# relay_dip_v01.net
KiCad netlist of a schematic drawn in EAGLE
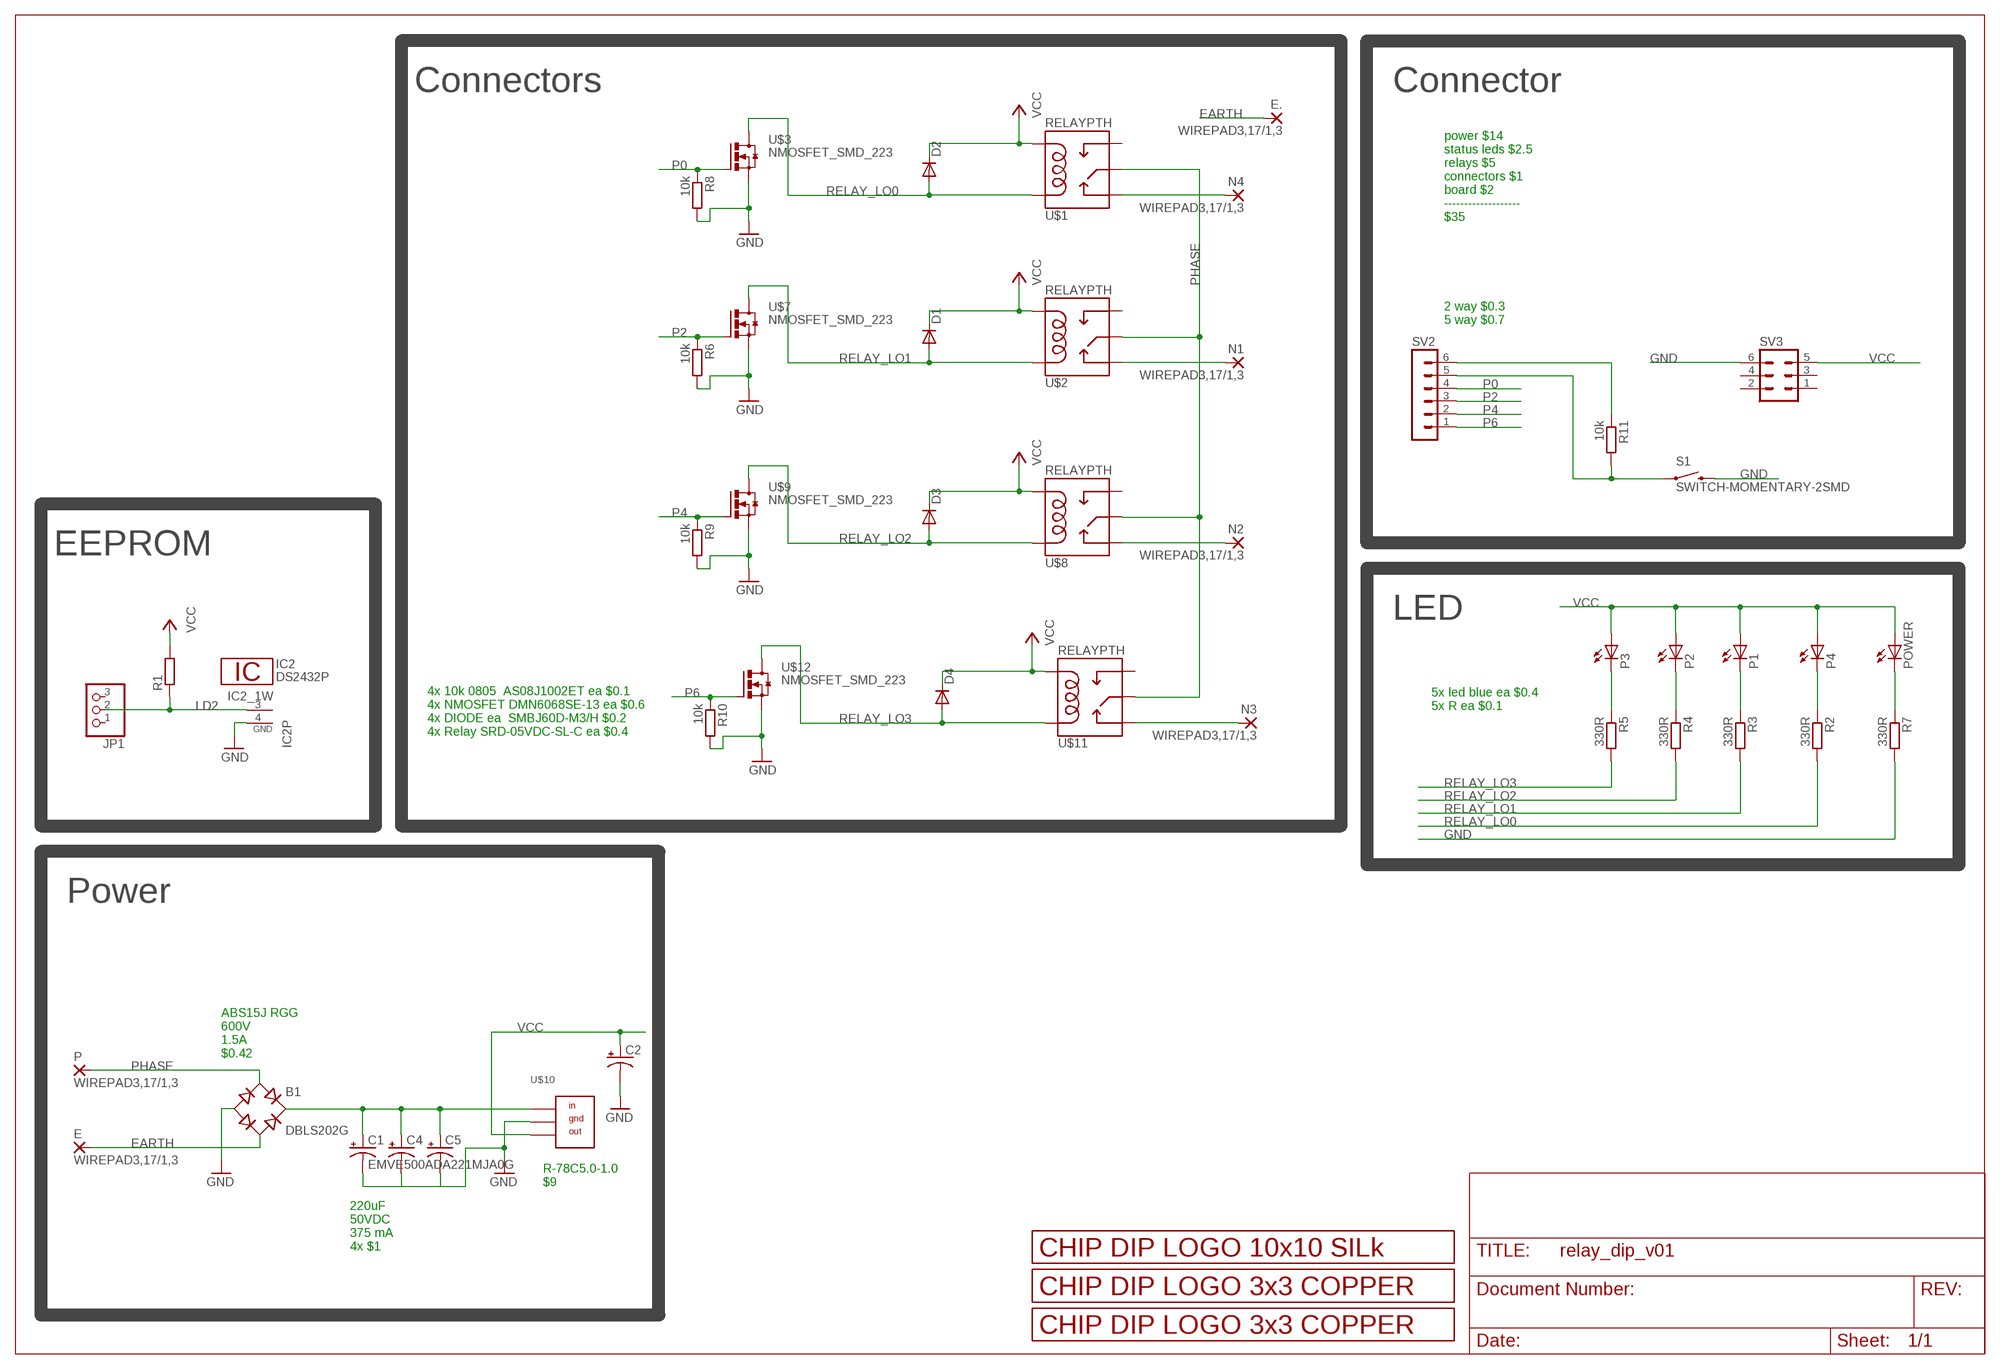
[diagram p0: schematic, sheet 1]

(export (version "E")
  (design (tool "Eeschema 10.0.6"))
  (components
    (comp (ref "B1")
      (value "DBLS202G")
      (footprint "eagle-import:DBS")
      (libsource (lib "eagle-import") (part "DB?GLS202"))
    )
    (comp (ref "C1")
      (value "EMVE500ADA221MJA0G")
      (footprint "eagle-import:150CLZ-0810")
      (libsource (lib "eagle-import") (part "CPOL-US150CLZ-0810"))
    )
    (comp (ref "C2")
      (value "CPOL-US150CLZ-0810")
      (footprint "eagle-import:150CLZ-0810")
      (libsource (lib "eagle-import") (part "CPOL-US150CLZ-0810"))
    )
    (comp (ref "C4")
      (value "CPOL-US150CLZ-0810")
      (footprint "eagle-import:150CLZ-0810")
      (libsource (lib "eagle-import") (part "CPOL-US150CLZ-0810"))
    )
    (comp (ref "C5")
      (value "CPOL-US150CLZ-0810")
      (footprint "eagle-import:150CLZ-0810")
      (libsource (lib "eagle-import") (part "CPOL-US150CLZ-0810"))
    )
    (comp (ref "D1")
      (value "DIODE-SMB")
      (footprint "eagle-import:SMB")
      (libsource (lib "eagle-import") (part "DIODE-SMB"))
    )
    (comp (ref "D2")
      (value "DIODE-SMB")
      (footprint "eagle-import:SMB")
      (libsource (lib "eagle-import") (part "DIODE-SMB"))
    )
    (comp (ref "D3")
      (value "DIODE-SMB")
      (footprint "eagle-import:SMB")
      (libsource (lib "eagle-import") (part "DIODE-SMB"))
    )
    (comp (ref "D4")
      (value "DIODE-SMB")
      (footprint "eagle-import:SMB")
      (libsource (lib "eagle-import") (part "DIODE-SMB"))
    )
    (comp (ref "E")
      (value "WIREPAD3,17/1,3")
      (footprint "eagle-import:3,17_1,3")
      (libsource (lib "eagle-import") (part "WIREPAD3,17/1,3"))
    )
    (comp (ref "E.")
      (value "WIREPAD3,17/1,3")
      (footprint "eagle-import:3,17_1,3")
      (libsource (lib "eagle-import") (part "WIREPAD3,17/1,3"))
    )
    (comp (ref "IC2")
      (value "DS2432P")
      (footprint "eagle-import:TSOC6")
      (libsource (lib "eagle-import") (part "DS2432P"))
    )
    (comp (ref "JP1")
      (value "PINHD-1X3")
      (footprint "eagle-import:1X03")
      (libsource (lib "eagle-import") (part "PINHD-1X3"))
    )
    (comp (ref "N1")
      (value "WIREPAD3,17/1,3")
      (footprint "eagle-import:3,17_1,3")
      (libsource (lib "eagle-import") (part "WIREPAD3,17/1,3"))
    )
    (comp (ref "N2")
      (value "WIREPAD3,17/1,3")
      (footprint "eagle-import:3,17_1,3")
      (libsource (lib "eagle-import") (part "WIREPAD3,17/1,3"))
    )
    (comp (ref "N3")
      (value "WIREPAD3,17/1,3")
      (footprint "eagle-import:3,17_1,3")
      (libsource (lib "eagle-import") (part "WIREPAD3,17/1,3"))
    )
    (comp (ref "N4")
      (value "WIREPAD3,17/1,3")
      (footprint "eagle-import:3,17_1,3")
      (libsource (lib "eagle-import") (part "WIREPAD3,17/1,3"))
    )
    (comp (ref "P")
      (value "WIREPAD3,17/1,3")
      (footprint "eagle-import:3,17_1,3")
      (libsource (lib "eagle-import") (part "WIREPAD3,17/1,3"))
    )
    (comp (ref "P1")
      (value "LEDCHIP-LED0805")
      (footprint "eagle-import:CHIP-LED0805")
      (libsource (lib "eagle-import") (part "LEDCHIP-LED0805"))
    )
    (comp (ref "P2")
      (value "LEDCHIP-LED0805")
      (footprint "eagle-import:CHIP-LED0805")
      (libsource (lib "eagle-import") (part "LEDCHIP-LED0805"))
    )
    (comp (ref "P3")
      (value "LEDCHIP-LED0805")
      (footprint "eagle-import:CHIP-LED0805")
      (libsource (lib "eagle-import") (part "LEDCHIP-LED0805"))
    )
    (comp (ref "P4")
      (value "LEDCHIP-LED0805")
      (footprint "eagle-import:CHIP-LED0805")
      (libsource (lib "eagle-import") (part "LEDCHIP-LED0805"))
    )
    (comp (ref "POWER")
      (value "LEDCHIP-LED0805")
      (footprint "eagle-import:CHIP-LED0805")
      (libsource (lib "eagle-import") (part "LEDCHIP-LED0805"))
    )
    (comp (ref "R1")
      (value "R-EU_R0805")
      (footprint "eagle-import:R0805")
      (libsource (lib "eagle-import") (part "R-EU_R0805"))
    )
    (comp (ref "R2")
      (value "330R")
      (footprint "eagle-import:R0805")
      (libsource (lib "eagle-import") (part "R-EU_R0805"))
    )
    (comp (ref "R3")
      (value "330R")
      (footprint "eagle-import:R0805")
      (libsource (lib "eagle-import") (part "R-EU_R0805"))
    )
    (comp (ref "R4")
      (value "330R")
      (footprint "eagle-import:R0805")
      (libsource (lib "eagle-import") (part "R-EU_R0805"))
    )
    (comp (ref "R5")
      (value "330R")
      (footprint "eagle-import:R0805")
      (libsource (lib "eagle-import") (part "R-EU_R0805"))
    )
    (comp (ref "R6")
      (value "10k")
      (footprint "eagle-import:R0805")
      (libsource (lib "eagle-import") (part "R-EU_R0805"))
    )
    (comp (ref "R7")
      (value "330R")
      (footprint "eagle-import:R0805")
      (libsource (lib "eagle-import") (part "R-EU_R0805"))
    )
    (comp (ref "R8")
      (value "10k")
      (footprint "eagle-import:R0805")
      (libsource (lib "eagle-import") (part "R-EU_R0805"))
    )
    (comp (ref "R9")
      (value "10k")
      (footprint "eagle-import:R0805")
      (libsource (lib "eagle-import") (part "R-EU_R0805"))
    )
    (comp (ref "R10")
      (value "10k")
      (footprint "eagle-import:R0805")
      (libsource (lib "eagle-import") (part "R-EU_R0805"))
    )
    (comp (ref "R11")
      (value "10k")
      (footprint "eagle-import:R0805")
      (libsource (lib "eagle-import") (part "R-EU_R0805"))
    )
    (comp (ref "S1")
      (value "SWITCH-MOMENTARY-2SMD")
      (footprint "eagle-import:TACTILE-SWITCH-SMD")
      (libsource (lib "eagle-import") (part "SWITCH-MOMENTARY-2SMD"))
    )
    (comp (ref "SV2")
      (value "MA06-1")
      (footprint "eagle-import:MA06-1")
      (libsource (lib "eagle-import") (part "MA06-1"))
    )
    (comp (ref "SV3")
      (value "MA03-2")
      (footprint "eagle-import:MA03-2")
      (libsource (lib "eagle-import") (part "MA03-2"))
    )
    (comp (ref "U$1")
      (value "RELAYPTH")
      (footprint "eagle-import:SRD-05VDC-SL-C")
      (libsource (lib "eagle-import") (part "RELAYPTH"))
    )
    (comp (ref "U$2")
      (value "RELAYPTH")
      (footprint "eagle-import:SRD-05VDC-SL-C")
      (libsource (lib "eagle-import") (part "RELAYPTH"))
    )
    (comp (ref "U$3")
      (value "NMOSFET_SMD_223")
      (footprint "eagle-import:SOT223")
      (libsource (lib "eagle-import") (part "NMOSFET_SMD_223"))
    )
    (comp (ref "U$4")
      (value "LOGO_3X3_COPPER")
      (footprint "eagle-import:LOGO_3X3_COPPER")
      (libsource (lib "eagle-import") (part "LOGO_3X3_COPPER"))
    )
    (comp (ref "U$5")
      (value "LOGO_10X10_SILK")
      (footprint "eagle-import:LOGO_10X10_SILK")
      (libsource (lib "eagle-import") (part "LOGO_10X10_SILK"))
    )
    (comp (ref "U$6")
      (value "LOGO_3X3_COPPER")
      (footprint "eagle-import:LOGO_3X3_COPPER")
      (libsource (lib "eagle-import") (part "LOGO_3X3_COPPER"))
    )
    (comp (ref "U$7")
      (value "NMOSFET_SMD_223")
      (footprint "eagle-import:SOT223")
      (libsource (lib "eagle-import") (part "NMOSFET_SMD_223"))
    )
    (comp (ref "U$8")
      (value "RELAYPTH")
      (footprint "eagle-import:SRD-05VDC-SL-C")
      (libsource (lib "eagle-import") (part "RELAYPTH"))
    )
    (comp (ref "U$9")
      (value "NMOSFET_SMD_223")
      (footprint "eagle-import:SOT223")
      (libsource (lib "eagle-import") (part "NMOSFET_SMD_223"))
    )
    (comp (ref "U$10")
      (value "R-7805-1.0")
      (footprint "eagle-import:SIP3")
      (libsource (lib "eagle-import") (part "R-7805-1.0"))
    )
    (comp (ref "U$11")
      (value "RELAYPTH")
      (footprint "eagle-import:SRD-05VDC-SL-C")
      (libsource (lib "eagle-import") (part "RELAYPTH"))
    )
    (comp (ref "U$12")
      (value "NMOSFET_SMD_223")
      (footprint "eagle-import:SOT223")
      (libsource (lib "eagle-import") (part "NMOSFET_SMD_223"))
    )
  )
  (nets
    (net (code "1") (name "/EARTH") (class "Default")
      (node (ref "B1") (pin "AC2") (pinfunction "AC2_AC2") (pintype "passive"))
      (node (ref "E") (pin "1") (pinfunction "P_1") (pintype "passive"))
      (node (ref "E.") (pin "1") (pinfunction "P_1") (pintype "passive"))
    )
    (net (code "2") (name "/LD2") (class "Default")
      (node (ref "IC2") (pin "3") (pinfunction "1W_3") (pintype "power_in"))
      (node (ref "JP1") (pin "2") (pinfunction "2_2") (pintype "passive"))
      (node (ref "R1") (pin "1") (pinfunction "1_1") (pintype "passive"))
    )
    (net (code "3") (name "/P0") (class "Default")
      (node (ref "R8") (pin "1") (pinfunction "1_1") (pintype "passive"))
      (node (ref "SV2") (pin "4") (pinfunction "4_4") (pintype "passive"))
      (node (ref "U$3") (pin "1") (pinfunction "G_1") (pintype "passive"))
    )
    (net (code "4") (name "/P2") (class "Default")
      (node (ref "R6") (pin "1") (pinfunction "1_1") (pintype "passive"))
      (node (ref "SV2") (pin "3") (pinfunction "3_3") (pintype "passive"))
      (node (ref "U$7") (pin "1") (pinfunction "G_1") (pintype "passive"))
    )
    (net (code "5") (name "/P4") (class "Default")
      (node (ref "R9") (pin "1") (pinfunction "1_1") (pintype "passive"))
      (node (ref "SV2") (pin "2") (pinfunction "2_2") (pintype "passive"))
      (node (ref "U$9") (pin "1") (pinfunction "G_1") (pintype "passive"))
    )
    (net (code "6") (name "/P6") (class "Default")
      (node (ref "R10") (pin "1") (pinfunction "1_1") (pintype "passive"))
      (node (ref "SV2") (pin "1") (pinfunction "1_1") (pintype "passive"))
      (node (ref "U$12") (pin "1") (pinfunction "G_1") (pintype "passive"))
    )
    (net (code "7") (name "/PHASE") (class "Default")
      (node (ref "B1") (pin "AC1") (pinfunction "AC1_AC1") (pintype "passive"))
      (node (ref "P") (pin "1") (pinfunction "P_1") (pintype "passive"))
      (node (ref "U$1") (pin "SWCOMMON") (pinfunction "SWCOMMON_SWCOMMON") (pintype "bidirectional"))
      (node (ref "U$11") (pin "SWCOMMON") (pinfunction "SWCOMMON_SWCOMMON") (pintype "bidirectional"))
      (node (ref "U$2") (pin "SWCOMMON") (pinfunction "SWCOMMON_SWCOMMON") (pintype "bidirectional"))
      (node (ref "U$8") (pin "SWCOMMON") (pinfunction "SWCOMMON_SWCOMMON") (pintype "bidirectional"))
    )
    (net (code "8") (name "/RELAY_LO0") (class "Default")
      (node (ref "D2") (pin "A") (pinfunction "A_A") (pintype "passive"))
      (node (ref "R2") (pin "2") (pinfunction "2_2") (pintype "passive"))
      (node (ref "U$1") (pin "COIL1") (pinfunction "COIL1_COIL1") (pintype "bidirectional"))
      (node (ref "U$3") (pin "2") (pinfunction "D_2") (pintype "passive"))
      (node (ref "U$3") (pin "4") (pinfunction "D_4") (pintype "passive"))
    )
    (net (code "9") (name "/RELAY_LO1") (class "Default")
      (node (ref "D1") (pin "A") (pinfunction "A_A") (pintype "passive"))
      (node (ref "R3") (pin "2") (pinfunction "2_2") (pintype "passive"))
      (node (ref "U$2") (pin "COIL1") (pinfunction "COIL1_COIL1") (pintype "bidirectional"))
      (node (ref "U$7") (pin "2") (pinfunction "D_2") (pintype "passive"))
      (node (ref "U$7") (pin "4") (pinfunction "D_4") (pintype "passive"))
    )
    (net (code "10") (name "/RELAY_LO2") (class "Default")
      (node (ref "D3") (pin "A") (pinfunction "A_A") (pintype "passive"))
      (node (ref "R4") (pin "2") (pinfunction "2_2") (pintype "passive"))
      (node (ref "U$8") (pin "COIL1") (pinfunction "COIL1_COIL1") (pintype "bidirectional"))
      (node (ref "U$9") (pin "2") (pinfunction "D_2") (pintype "passive"))
      (node (ref "U$9") (pin "4") (pinfunction "D_4") (pintype "passive"))
    )
    (net (code "11") (name "/RELAY_LO3") (class "Default")
      (node (ref "D4") (pin "A") (pinfunction "A_A") (pintype "passive"))
      (node (ref "R5") (pin "2") (pinfunction "2_2") (pintype "passive"))
      (node (ref "U$11") (pin "COIL1") (pinfunction "COIL1_COIL1") (pintype "bidirectional"))
      (node (ref "U$12") (pin "2") (pinfunction "D_2") (pintype "passive"))
      (node (ref "U$12") (pin "4") (pinfunction "D_4") (pintype "passive"))
    )
    (net (code "12") (name "GND") (class "Default")
      (node (ref "B1") (pin "-") (pinfunction "-_-") (pintype "passive"))
      (node (ref "C1") (pin "-") (pinfunction "-_-") (pintype "passive"))
      (node (ref "C2") (pin "-") (pinfunction "-_-") (pintype "passive"))
      (node (ref "C4") (pin "-") (pinfunction "-_-") (pintype "passive"))
      (node (ref "C5") (pin "-") (pinfunction "-_-") (pintype "passive"))
      (node (ref "IC2") (pin "4") (pinfunction "GND_4") (pintype "power_in"))
      (node (ref "R10") (pin "2") (pinfunction "2_2") (pintype "passive"))
      (node (ref "R6") (pin "2") (pinfunction "2_2") (pintype "passive"))
      (node (ref "R7") (pin "2") (pinfunction "2_2") (pintype "passive"))
      (node (ref "R8") (pin "2") (pinfunction "2_2") (pintype "passive"))
      (node (ref "R9") (pin "2") (pinfunction "2_2") (pintype "passive"))
      (node (ref "S1") (pin "3") (pinfunction "2_3") (pintype "passive"))
      (node (ref "SV3") (pin "6") (pinfunction "6_6") (pintype "passive"))
      (node (ref "U$10") (pin "GND") (pinfunction "GND_GND") (pintype "bidirectional"))
      (node (ref "U$12") (pin "3") (pinfunction "S_3") (pintype "passive"))
      (node (ref "U$3") (pin "3") (pinfunction "S_3") (pintype "passive"))
      (node (ref "U$7") (pin "3") (pinfunction "S_3") (pintype "passive"))
      (node (ref "U$9") (pin "3") (pinfunction "S_3") (pintype "passive"))
    )
    (net (code "13") (name "Net-(B1-Pad+)") (class "Default")
      (node (ref "B1") (pin "+") (pinfunction "+_+") (pintype "passive"))
      (node (ref "C1") (pin "+") (pinfunction "+_+") (pintype "passive"))
      (node (ref "C4") (pin "+") (pinfunction "+_+") (pintype "passive"))
      (node (ref "C5") (pin "+") (pinfunction "+_+") (pintype "passive"))
      (node (ref "U$10") (pin "IN") (pinfunction "IN_IN") (pintype "bidirectional"))
    )
    (net (code "14") (name "Net-(N1-P)") (class "Default")
      (node (ref "N1") (pin "1") (pinfunction "P_1") (pintype "passive"))
      (node (ref "U$2") (pin "SWCLOSED") (pinfunction "SWCLOSE_SWCLOSED") (pintype "bidirectional"))
    )
    (net (code "15") (name "Net-(N2-P)") (class "Default")
      (node (ref "N2") (pin "1") (pinfunction "P_1") (pintype "passive"))
      (node (ref "U$8") (pin "SWCLOSED") (pinfunction "SWCLOSE_SWCLOSED") (pintype "bidirectional"))
    )
    (net (code "16") (name "Net-(N3-P)") (class "Default")
      (node (ref "N3") (pin "1") (pinfunction "P_1") (pintype "passive"))
      (node (ref "U$11") (pin "SWCLOSED") (pinfunction "SWCLOSE_SWCLOSED") (pintype "bidirectional"))
    )
    (net (code "17") (name "Net-(N4-P)") (class "Default")
      (node (ref "N4") (pin "1") (pinfunction "P_1") (pintype "passive"))
      (node (ref "U$1") (pin "SWCLOSED") (pinfunction "SWCLOSE_SWCLOSED") (pintype "bidirectional"))
    )
    (net (code "18") (name "Net-(P1-PadC)") (class "Default")
      (node (ref "P1") (pin "C") (pinfunction "C_C") (pintype "passive"))
      (node (ref "R3") (pin "1") (pinfunction "1_1") (pintype "passive"))
    )
    (net (code "19") (name "Net-(P2-PadC)") (class "Default")
      (node (ref "P2") (pin "C") (pinfunction "C_C") (pintype "passive"))
      (node (ref "R4") (pin "1") (pinfunction "1_1") (pintype "passive"))
    )
    (net (code "20") (name "Net-(P3-PadC)") (class "Default")
      (node (ref "P3") (pin "C") (pinfunction "C_C") (pintype "passive"))
      (node (ref "R5") (pin "1") (pinfunction "1_1") (pintype "passive"))
    )
    (net (code "21") (name "Net-(P4-PadC)") (class "Default")
      (node (ref "P4") (pin "C") (pinfunction "C_C") (pintype "passive"))
      (node (ref "R2") (pin "1") (pinfunction "1_1") (pintype "passive"))
    )
    (net (code "22") (name "Net-(POWER-PadC)") (class "Default")
      (node (ref "POWER") (pin "C") (pinfunction "C_C") (pintype "passive"))
      (node (ref "R7") (pin "1") (pinfunction "1_1") (pintype "passive"))
    )
    (net (code "23") (name "Net-(R11-Pad1)") (class "Default")
      (node (ref "R11") (pin "1") (pinfunction "1_1") (pintype "passive"))
      (node (ref "SV2") (pin "6") (pinfunction "6_6") (pintype "passive"))
    )
    (net (code "24") (name "Net-(R11-Pad2)") (class "Default")
      (node (ref "R11") (pin "2") (pinfunction "2_2") (pintype "passive"))
      (node (ref "S1") (pin "1") (pinfunction "1_1") (pintype "passive"))
      (node (ref "SV2") (pin "5") (pinfunction "5_5") (pintype "passive"))
    )
    (net (code "25") (name "VCC") (class "Default")
      (node (ref "C2") (pin "+") (pinfunction "+_+") (pintype "passive"))
      (node (ref "D1") (pin "C") (pinfunction "C_C") (pintype "passive"))
      (node (ref "D2") (pin "C") (pinfunction "C_C") (pintype "passive"))
      (node (ref "D3") (pin "C") (pinfunction "C_C") (pintype "passive"))
      (node (ref "D4") (pin "C") (pinfunction "C_C") (pintype "passive"))
      (node (ref "P1") (pin "A") (pinfunction "A_A") (pintype "passive"))
      (node (ref "P2") (pin "A") (pinfunction "A_A") (pintype "passive"))
      (node (ref "P3") (pin "A") (pinfunction "A_A") (pintype "passive"))
      (node (ref "P4") (pin "A") (pinfunction "A_A") (pintype "passive"))
      (node (ref "POWER") (pin "A") (pinfunction "A_A") (pintype "passive"))
      (node (ref "R1") (pin "2") (pinfunction "2_2") (pintype "passive"))
      (node (ref "SV3") (pin "5") (pinfunction "5_5") (pintype "passive"))
      (node (ref "U$1") (pin "COIL0") (pinfunction "COIL0_COIL0") (pintype "bidirectional"))
      (node (ref "U$10") (pin "OUT") (pinfunction "OUT_OUT") (pintype "bidirectional"))
      (node (ref "U$11") (pin "COIL0") (pinfunction "COIL0_COIL0") (pintype "bidirectional"))
      (node (ref "U$2") (pin "COIL0") (pinfunction "COIL0_COIL0") (pintype "bidirectional"))
      (node (ref "U$8") (pin "COIL0") (pinfunction "COIL0_COIL0") (pintype "bidirectional"))
    )
    (net (code "26") (name "unconnected-(JP1-Pad1)") (class "Default")
      (node (ref "JP1") (pin "1") (pinfunction "1_1") (pintype "passive"))
    )
    (net (code "27") (name "unconnected-(JP1-Pad3)") (class "Default")
      (node (ref "JP1") (pin "3") (pinfunction "3_3") (pintype "passive"))
    )
    (net (code "28") (name "unconnected-(SV3-Pad1)") (class "Default")
      (node (ref "SV3") (pin "1") (pinfunction "1_1") (pintype "passive"))
    )
    (net (code "29") (name "unconnected-(SV3-Pad2)") (class "Default")
      (node (ref "SV3") (pin "2") (pinfunction "2_2") (pintype "passive"))
    )
    (net (code "30") (name "unconnected-(SV3-Pad3)") (class "Default")
      (node (ref "SV3") (pin "3") (pinfunction "3_3") (pintype "passive"))
    )
    (net (code "31") (name "unconnected-(SV3-Pad4)") (class "Default")
      (node (ref "SV3") (pin "4") (pinfunction "4_4") (pintype "passive"))
    )
    (net (code "32") (name "unconnected-(U$1-PadSWOPEN)") (class "Default")
      (node (ref "U$1") (pin "SWOPEN") (pinfunction "SWOPEN_SWOPEN") (pintype "bidirectional"))
    )
    (net (code "33") (name "unconnected-(U$2-PadSWOPEN)") (class "Default")
      (node (ref "U$2") (pin "SWOPEN") (pinfunction "SWOPEN_SWOPEN") (pintype "bidirectional"))
    )
    (net (code "34") (name "unconnected-(U$8-PadSWOPEN)") (class "Default")
      (node (ref "U$8") (pin "SWOPEN") (pinfunction "SWOPEN_SWOPEN") (pintype "bidirectional"))
    )
    (net (code "35") (name "unconnected-(U$11-PadSWOPEN)") (class "Default")
      (node (ref "U$11") (pin "SWOPEN") (pinfunction "SWOPEN_SWOPEN") (pintype "bidirectional"))
    )
  )
)
